# PowerSupply.net
KiCad netlist of a schematic drawn in Altium Designer
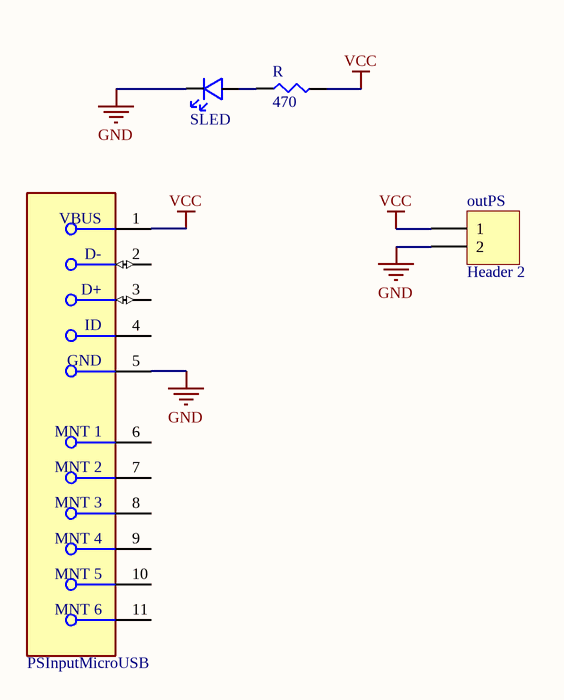
[diagram p0: PowerSupply.SchDoc]

(export (version "E")
  (design (tool "Eeschema 10.0.6"))
  (components
    (comp (ref "outPS")
      (value "Header 2")
      (footprint "HDR1X2")
      (description "Header, 2-Pin")
      (fields (field (name "PUBLISHER") "Altium Limited"))
      (libsource (lib "Miscellaneous Connectors") (part "Header 2"))
    )
    (comp (ref "PSInputMicroUSB")
      (value "473460001")
      (footprint "Molex_0_MFG")
      (description "USB - micro B USB 2.0 Receptacle Connector 5 Position Surface Mount, Right Angle")
      (fields (field (name "DIGIKEY PART NUMBER") "WM17141CT-ND") (field (name "MANUFACTURER") "Molex"))
      (libsource (lib "EEConcierge") (part "473460001"))
    )
    (comp (ref "R")
      (value "470")
      (footprint "SMD-1206-RES")
      (description "RES SMD 470 OHM 5% 1/4W 1206")
      (fields (field (name "PART NUMBER") "ERJ-8GEYJ471V") (field (name "DIGI-KEY PART NUMBER") "P470ECT-ND"))
      (libsource (lib "Panasonic_ERJ_1206") (part "ERJ-8GEYJ471V"))
    )
    (comp (ref "SLED") (value "LED") (footprint "SMD-1206-RES") (libsource (lib "LED") (part "LED")))
  )
  (nets
    (net (code "1") (name "GND") (class "Default")
      (node (ref "PSInputMicroUSB") (pin "5") (pinfunction "GND_5") (pintype "power_in"))
      (node (ref "SLED") (pin "2") (pinfunction "2_2") (pintype "passive"))
      (node (ref "outPS") (pin "2") (pinfunction "2_2") (pintype "passive"))
    )
    (net (code "2") (name "Net-(R-Pad1)") (class "Default")
      (node (ref "R") (pin "1") (pinfunction "1_1") (pintype "passive"))
      (node (ref "SLED") (pin "1") (pinfunction "1_1") (pintype "passive"))
    )
    (net (code "3") (name "VCC") (class "Default")
      (node (ref "PSInputMicroUSB") (pin "1") (pinfunction "VBUS_1") (pintype "power_in"))
      (node (ref "R") (pin "2") (pinfunction "2_2") (pintype "passive"))
      (node (ref "outPS") (pin "1") (pinfunction "1_1") (pintype "passive"))
    )
    (net (code "4") (name "unconnected-(PSInputMicroUSB-D+-Pad3)") (class "Default")
      (node (ref "PSInputMicroUSB") (pin "3") (pinfunction "D+_3") (pintype "bidirectional"))
    )
    (net (code "5") (name "unconnected-(PSInputMicroUSB-D--Pad2)") (class "Default")
      (node (ref "PSInputMicroUSB") (pin "2") (pinfunction "D-_2") (pintype "bidirectional"))
    )
    (net (code "6") (name "unconnected-(PSInputMicroUSB-ID-Pad4)") (class "Default")
      (node (ref "PSInputMicroUSB") (pin "4") (pinfunction "ID_4") (pintype "passive"))
    )
    (net (code "7") (name "unconnected-(PSInputMicroUSB-MNT_1-Pad6)") (class "Default")
      (node (ref "PSInputMicroUSB") (pin "6") (pinfunction "MNT_1_6") (pintype "passive"))
    )
    (net (code "8") (name "unconnected-(PSInputMicroUSB-MNT_2-Pad7)") (class "Default")
      (node (ref "PSInputMicroUSB") (pin "7") (pinfunction "MNT_2_7") (pintype "passive"))
    )
    (net (code "9") (name "unconnected-(PSInputMicroUSB-MNT_3-Pad8)") (class "Default")
      (node (ref "PSInputMicroUSB") (pin "8") (pinfunction "MNT_3_8") (pintype "passive"))
    )
    (net (code "10") (name "unconnected-(PSInputMicroUSB-MNT_4-Pad9)") (class "Default")
      (node (ref "PSInputMicroUSB") (pin "9") (pinfunction "MNT_4_9") (pintype "passive"))
    )
    (net (code "11") (name "unconnected-(PSInputMicroUSB-MNT_5-Pad10)") (class "Default")
      (node (ref "PSInputMicroUSB") (pin "10") (pinfunction "MNT_5_10") (pintype "passive"))
    )
    (net (code "12") (name "unconnected-(PSInputMicroUSB-MNT_6-Pad11)") (class "Default")
      (node (ref "PSInputMicroUSB") (pin "11") (pinfunction "MNT_6_11") (pintype "passive"))
    )
  )
)
